# baseboard.net
KiCad netlist of a schematic drawn in EAGLE
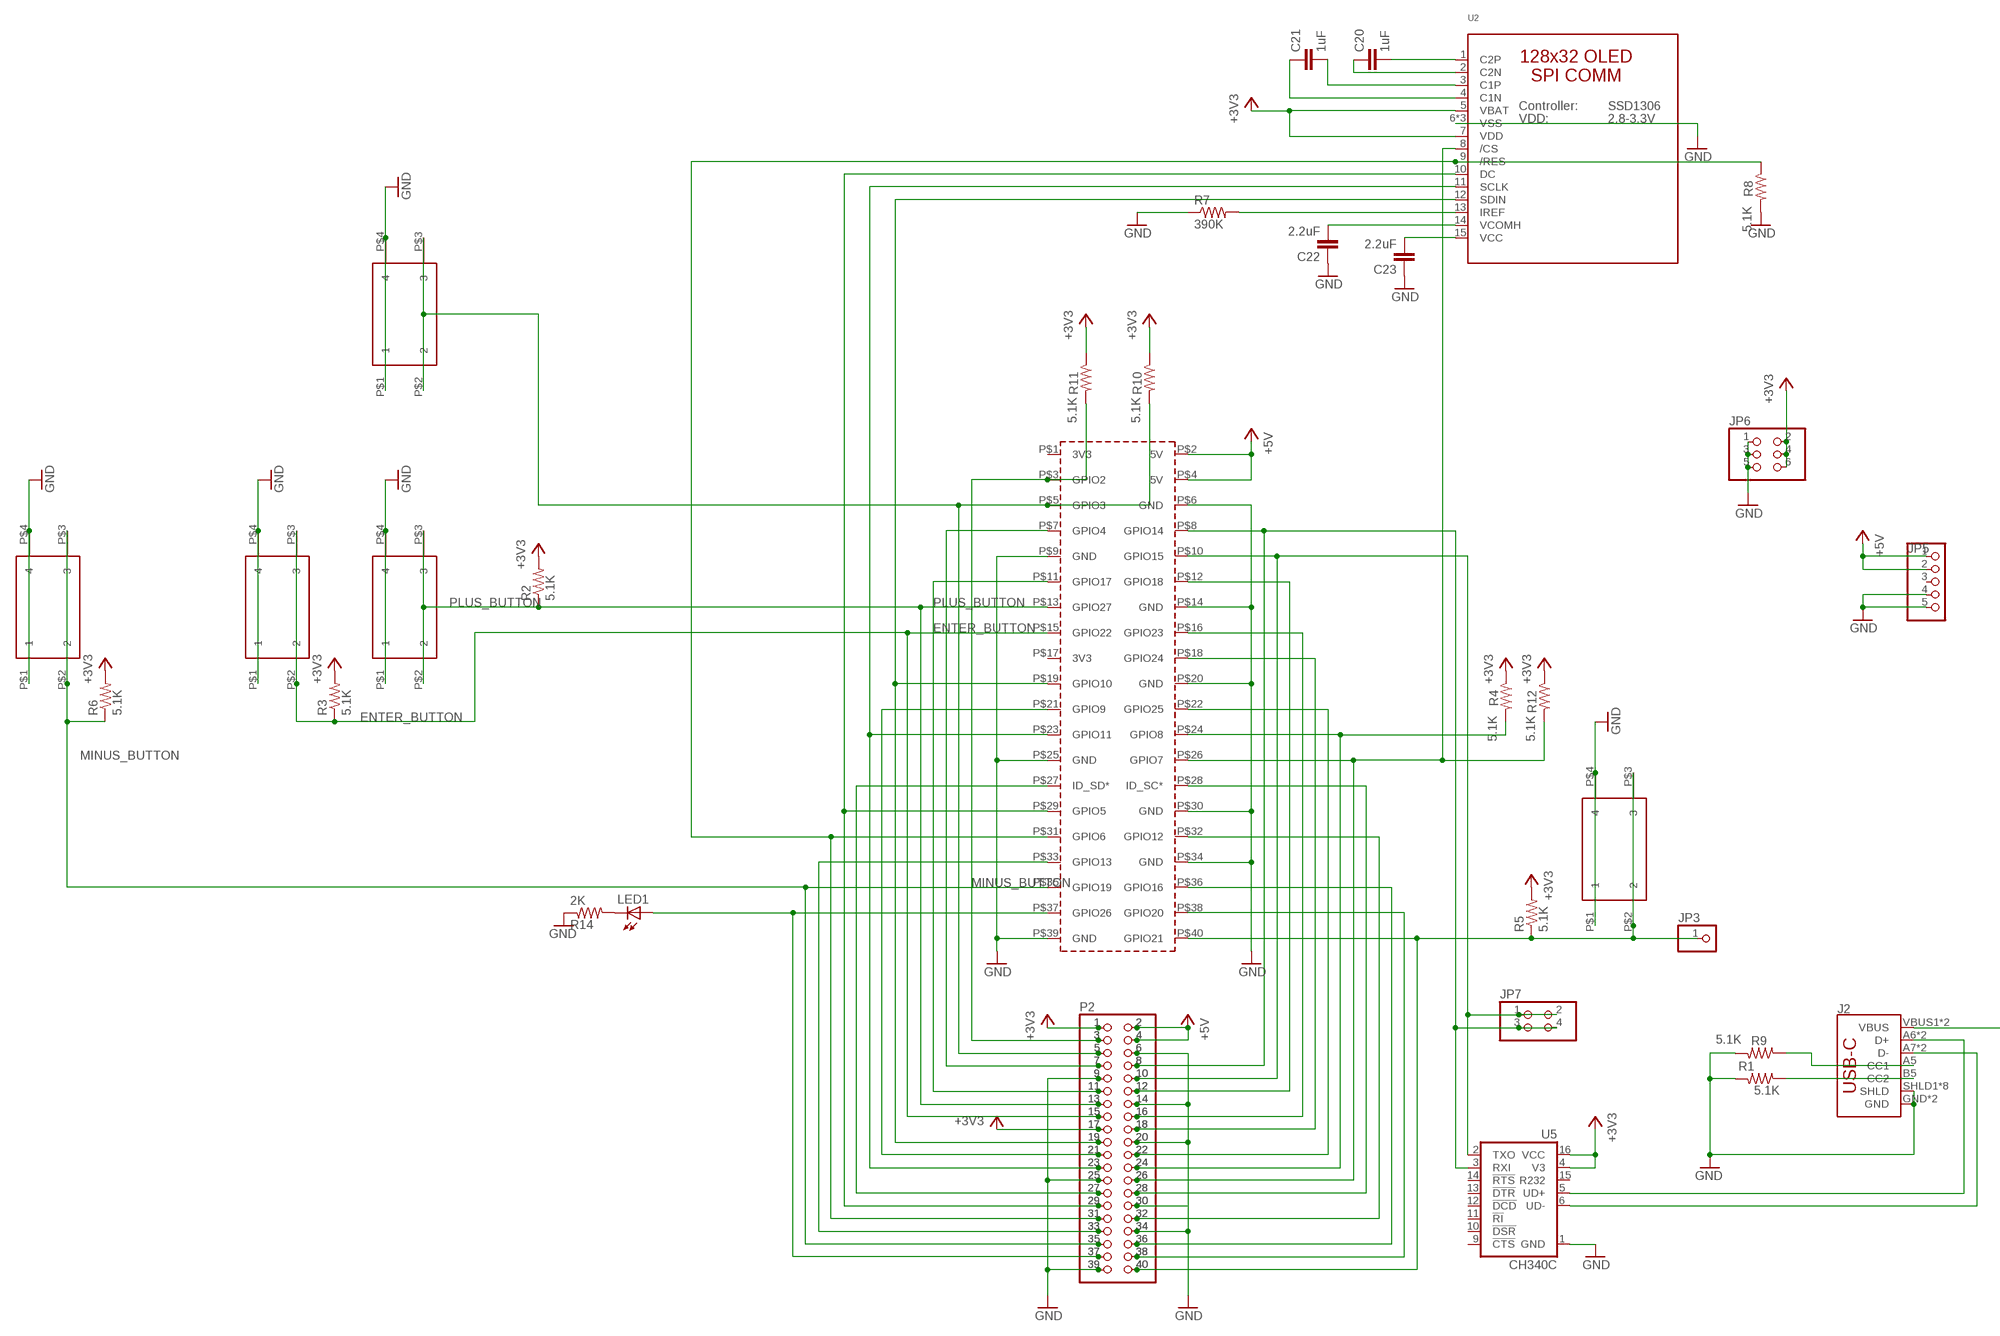
[diagram p0: schematic, sheet 1, part 1 of 2]
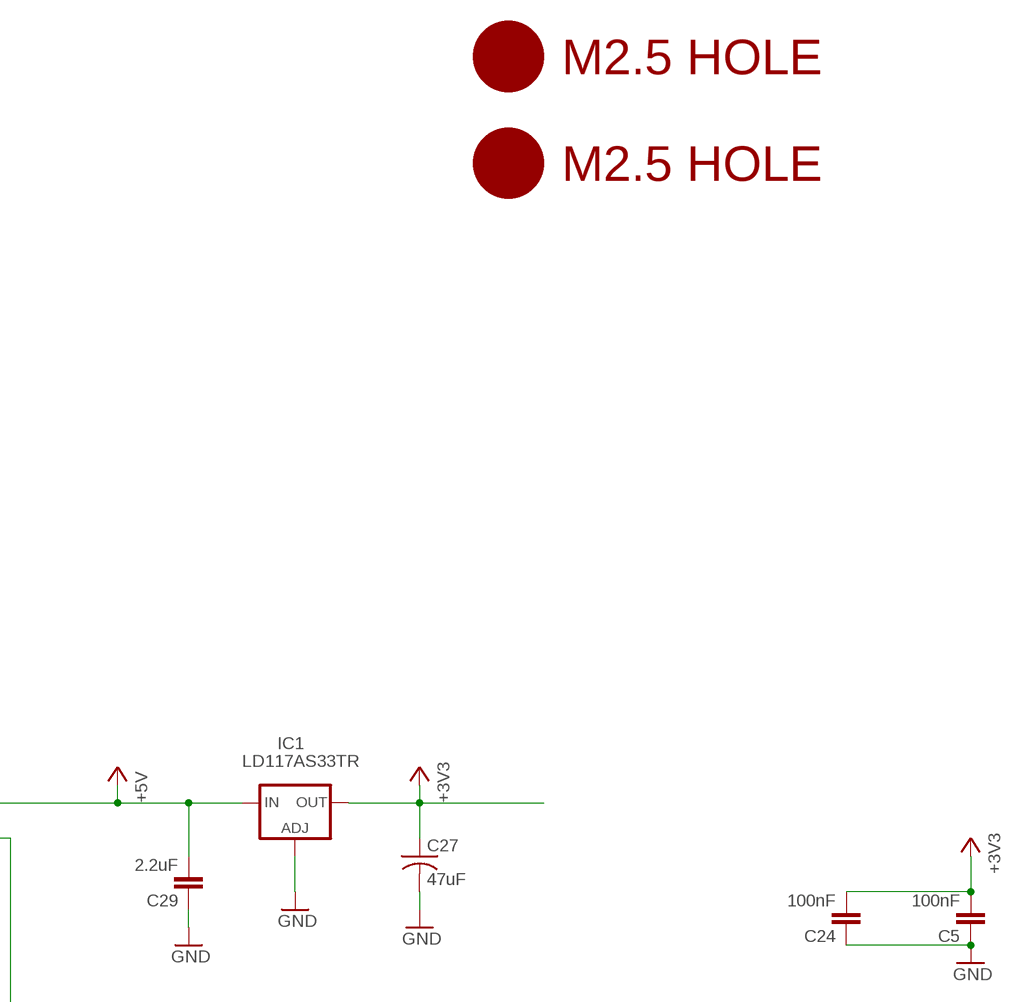
[diagram p1: schematic, sheet 1, part 2 of 2]

(export (version "E")
  (design (tool "Eeschema 10.0.6"))
  (components
    (comp (ref "C5")
      (value "100nF")
      (footprint "eagle-import:0805")
      (libsource (lib "eagle-import") (part "CAP0805"))
    )
    (comp (ref "C20")
      (value "1uF")
      (footprint "eagle-import:0805")
      (libsource (lib "eagle-import") (part "CAP0805"))
    )
    (comp (ref "C21")
      (value "1uF")
      (footprint "eagle-import:0805")
      (libsource (lib "eagle-import") (part "CAP0805"))
    )
    (comp (ref "C22")
      (value "2.2uF")
      (footprint "eagle-import:0805")
      (libsource (lib "eagle-import") (part "CAP0805"))
    )
    (comp (ref "C23")
      (value "2.2uF")
      (footprint "eagle-import:0805")
      (libsource (lib "eagle-import") (part "CAP0805"))
    )
    (comp (ref "C24")
      (value "100nF")
      (footprint "eagle-import:0805")
      (libsource (lib "eagle-import") (part "CAP0805"))
    )
    (comp (ref "C27")
      (value "47uF")
      (footprint "eagle-import:C1210")
      (libsource (lib "eagle-import") (part "C-USC1210"))
    )
    (comp (ref "C29")
      (value "2.2uF")
      (footprint "eagle-import:0805")
      (libsource (lib "eagle-import") (part "CAP0805"))
    )
    (comp (ref "IC1")
      (value "LD117AS33TR")
      (footprint "eagle-import:SOT223")
      (libsource (lib "eagle-import") (part "LD117A?S33TR"))
    )
    (comp (ref "J2")
      (value "USB_C16PIN")
      (footprint "eagle-import:USB-C-16P")
      (libsource (lib "eagle-import") (part "USB_C16PIN"))
    )
    (comp (ref "JP3")
      (value "PINHD-1X1")
      (footprint "eagle-import:1X01")
      (libsource (lib "eagle-import") (part "PINHD-1X1"))
    )
    (comp (ref "JP5")
      (value "PINHD-1X5")
      (footprint "eagle-import:1X05")
      (libsource (lib "eagle-import") (part "PINHD-1X5"))
    )
    (comp (ref "JP6")
      (value "PINHD-2X3")
      (footprint "eagle-import:2X03")
      (libsource (lib "eagle-import") (part "PINHD-2X3"))
    )
    (comp (ref "JP7")
      (value "PINHD-2X2")
      (footprint "eagle-import:2X02")
      (libsource (lib "eagle-import") (part "PINHD-2X2"))
    )
    (comp (ref "LED1")
      (value "LEDCHIP-LED0805")
      (footprint "eagle-import:CHIP-LED0805")
      (libsource (lib "eagle-import") (part "LEDCHIP-LED0805"))
    )
    (comp (ref "P1")
      (value "RPI3NO-CONNECTORS")
      (footprint "eagle-import:RPI3-NO-CONNECTORS")
      (libsource (lib "eagle-import") (part "RPI3NO-CONNECTORS"))
    )
    (comp (ref "P2")
      (value "PINHD-2X20-BIG")
      (footprint "eagle-import:2X20-BIG")
      (libsource (lib "eagle-import") (part "PINHD-2X20-BIG"))
    )
    (comp (ref "P3")
      (value "PINHD-2X20-BIG")
      (footprint "eagle-import:2X20-BIG")
      (libsource (lib "eagle-import") (part "PINHD-2X20-BIG"))
    )
    (comp (ref "R1")
      (value "5.1K")
      (footprint "eagle-import:0805")
      (libsource (lib "eagle-import") (part "joyAnalog_RESISTOR0805-RES"))
    )
    (comp (ref "R2")
      (value "5.1K")
      (footprint "eagle-import:0805")
      (libsource (lib "eagle-import") (part "RESISTOR0805-RES"))
    )
    (comp (ref "R3")
      (value "5.1K")
      (footprint "eagle-import:0805")
      (libsource (lib "eagle-import") (part "RESISTOR0805-RES"))
    )
    (comp (ref "R4")
      (value "5.1K")
      (footprint "eagle-import:0805")
      (libsource (lib "eagle-import") (part "joyAnalog_RESISTOR0805-RES"))
    )
    (comp (ref "R5")
      (value "5.1K")
      (footprint "eagle-import:0805")
      (libsource (lib "eagle-import") (part "RESISTOR0805-RES"))
    )
    (comp (ref "R6")
      (value "5.1K")
      (footprint "eagle-import:0805")
      (libsource (lib "eagle-import") (part "RESISTOR0805-RES"))
    )
    (comp (ref "R7")
      (value "390K")
      (footprint "eagle-import:0805")
      (libsource (lib "eagle-import") (part "RESISTOR0805-RES"))
    )
    (comp (ref "R8")
      (value "5.1K")
      (footprint "eagle-import:0805")
      (libsource (lib "eagle-import") (part "joyAnalog_RESISTOR0805-RES"))
    )
    (comp (ref "R9")
      (value "5.1K")
      (footprint "eagle-import:0805")
      (libsource (lib "eagle-import") (part "joyAnalog_RESISTOR0805-RES"))
    )
    (comp (ref "R10")
      (value "5.1K")
      (footprint "eagle-import:0805")
      (libsource (lib "eagle-import") (part "joyAnalog_RESISTOR0805-RES"))
    )
    (comp (ref "R11")
      (value "5.1K")
      (footprint "eagle-import:0805")
      (libsource (lib "eagle-import") (part "joyAnalog_RESISTOR0805-RES"))
    )
    (comp (ref "R12")
      (value "5.1K")
      (footprint "eagle-import:0805")
      (libsource (lib "eagle-import") (part "joyAnalog_RESISTOR0805-RES"))
    )
    (comp (ref "R14")
      (value "2K")
      (footprint "eagle-import:0805")
      (libsource (lib "eagle-import") (part "RESISTOR0805-RES"))
    )
    (comp (ref "SW1")
      (value "324_SW")
      (footprint "eagle-import:342_SWICH_FOOT")
      (libsource (lib "eagle-import") (part "324_SW"))
    )
    (comp (ref "SW2")
      (value "324_SW")
      (footprint "eagle-import:342_SWICH_FOOT")
      (libsource (lib "eagle-import") (part "324_SW"))
    )
    (comp (ref "SW3")
      (value "324_SW")
      (footprint "eagle-import:342_SWICH_FOOT")
      (libsource (lib "eagle-import") (part "324_SW"))
    )
    (comp (ref "SW4")
      (value "324_SW")
      (footprint "eagle-import:342_SWICH_FOOT")
      (libsource (lib "eagle-import") (part "324_SW"))
    )
    (comp (ref "SW20")
      (value "324_SW")
      (footprint "eagle-import:342_SWICH_FOOT")
      (libsource (lib "eagle-import") (part "324_SW"))
    )
    (comp (ref "U$2")
      (value "M2.5HOLE")
      (footprint "eagle-import:M2.5HOLE")
      (libsource (lib "eagle-import") (part "M2.5HOLE"))
    )
    (comp (ref "U$3")
      (value "M2.5HOLE")
      (footprint "eagle-import:M2.5HOLE")
      (libsource (lib "eagle-import") (part "M2.5HOLE"))
    )
    (comp (ref "U2")
      (value "LUL_DISP_OLED_UG-2864HSWEG01")
      (footprint "eagle-import:LUL_UG-2864HSWEG01_1.3_WRAPAROUND")
      (libsource (lib "eagle-import") (part "LUL_DISP_OLED_UG-2864HSWEG01"))
    )
    (comp (ref "U5")
      (value "CH340C")
      (footprint "eagle-import:SO016")
      (libsource (lib "eagle-import") (part "CH340C"))
    )
  )
  (nets
    (net (code "1") (name "+3V3") (class "Default")
      (node (ref "C24") (pin "2") (pinfunction "2_2") (pintype "passive"))
      (node (ref "C27") (pin "1") (pinfunction "1_1") (pintype "passive"))
      (node (ref "C5") (pin "2") (pinfunction "2_2") (pintype "passive"))
      (node (ref "IC1") (pin "4") (pinfunction "OUT_4") (pintype "passive"))
      (node (ref "JP6") (pin "2") (pinfunction "2_2") (pintype "passive"))
      (node (ref "JP6") (pin "4") (pinfunction "4_4") (pintype "passive"))
      (node (ref "JP6") (pin "6") (pinfunction "6_6") (pintype "passive"))
      (node (ref "P2") (pin "1") (pinfunction "1_1") (pintype "passive"))
      (node (ref "P2") (pin "17") (pinfunction "17_17") (pintype "passive"))
      (node (ref "P3") (pin "1") (pinfunction "1_1") (pintype "passive"))
      (node (ref "P3") (pin "17") (pinfunction "17_17") (pintype "passive"))
      (node (ref "R10") (pin "1") (pinfunction "1_1") (pintype "passive"))
      (node (ref "R11") (pin "1") (pinfunction "1_1") (pintype "passive"))
      (node (ref "R12") (pin "1") (pinfunction "1_1") (pintype "passive"))
      (node (ref "R2") (pin "2") (pinfunction "2_2") (pintype "passive"))
      (node (ref "R3") (pin "2") (pinfunction "2_2") (pintype "passive"))
      (node (ref "R4") (pin "1") (pinfunction "1_1") (pintype "passive"))
      (node (ref "R5") (pin "2") (pinfunction "2_2") (pintype "passive"))
      (node (ref "R6") (pin "2") (pinfunction "2_2") (pintype "passive"))
      (node (ref "U2") (pin "5") (pinfunction "VBAT_5") (pintype "input"))
      (node (ref "U2") (pin "7") (pinfunction "VDD_7") (pintype "power_in"))
      (node (ref "U5") (pin "16") (pinfunction "VCC_16") (pintype "bidirectional"))
      (node (ref "U5") (pin "4") (pinfunction "V3_4") (pintype "bidirectional"))
    )
    (net (code "2") (name "+5V") (class "Default")
      (node (ref "C29") (pin "2") (pinfunction "2_2") (pintype "passive"))
      (node (ref "IC1") (pin "3") (pinfunction "IN_3") (pintype "input"))
      (node (ref "J2") (pin "VBUS1") (pinfunction "VBUS_VBUS1") (pintype "bidirectional"))
      (node (ref "J2") (pin "VBUS2") (pinfunction "VBUS_VBUS2") (pintype "bidirectional"))
      (node (ref "JP5") (pin "1") (pinfunction "1_1") (pintype "passive"))
      (node (ref "JP5") (pin "2") (pinfunction "2_2") (pintype "passive"))
      (node (ref "P1") (pin "P$2") (pinfunction "5V_P$2") (pintype "bidirectional"))
      (node (ref "P1") (pin "P$4") (pinfunction "5V_P$4") (pintype "bidirectional"))
      (node (ref "P2") (pin "2") (pinfunction "2_2") (pintype "passive"))
      (node (ref "P2") (pin "4") (pinfunction "4_4") (pintype "passive"))
      (node (ref "P3") (pin "2") (pinfunction "2_2") (pintype "passive"))
      (node (ref "P3") (pin "4") (pinfunction "4_4") (pintype "passive"))
    )
    (net (code "3") (name "/ENTER_BUTTON") (class "Default")
      (node (ref "P1") (pin "P$15") (pinfunction "GPIO22_P$15") (pintype "bidirectional"))
      (node (ref "P2") (pin "15") (pinfunction "15_15") (pintype "passive"))
      (node (ref "P3") (pin "15") (pinfunction "15_15") (pintype "passive"))
      (node (ref "R3") (pin "1") (pinfunction "1_1") (pintype "passive"))
      (node (ref "SW20") (pin "P$2") (pinfunction "2_P$2") (pintype "bidirectional"))
      (node (ref "SW20") (pin "P$3") (pinfunction "3_P$3") (pintype "bidirectional"))
    )
    (net (code "4") (name "/MINUS_BUTTON") (class "Default")
      (node (ref "P1") (pin "P$35") (pinfunction "GPIO19_P$35") (pintype "bidirectional"))
      (node (ref "P2") (pin "35") (pinfunction "35_35") (pintype "passive"))
      (node (ref "P3") (pin "35") (pinfunction "35_35") (pintype "passive"))
      (node (ref "R6") (pin "1") (pinfunction "1_1") (pintype "passive"))
      (node (ref "SW4") (pin "P$2") (pinfunction "2_P$2") (pintype "bidirectional"))
      (node (ref "SW4") (pin "P$3") (pinfunction "3_P$3") (pintype "bidirectional"))
    )
    (net (code "5") (name "/PLUS_BUTTON") (class "Default")
      (node (ref "P1") (pin "P$13") (pinfunction "GPIO27_P$13") (pintype "bidirectional"))
      (node (ref "P2") (pin "13") (pinfunction "13_13") (pintype "passive"))
      (node (ref "P3") (pin "13") (pinfunction "13_13") (pintype "passive"))
      (node (ref "R2") (pin "1") (pinfunction "1_1") (pintype "passive"))
      (node (ref "SW1") (pin "P$2") (pinfunction "2_P$2") (pintype "bidirectional"))
      (node (ref "SW1") (pin "P$3") (pinfunction "3_P$3") (pintype "bidirectional"))
    )
    (net (code "6") (name "GND") (class "Default")
      (node (ref "C22") (pin "1") (pinfunction "1_1") (pintype "passive"))
      (node (ref "C23") (pin "1") (pinfunction "1_1") (pintype "passive"))
      (node (ref "C24") (pin "1") (pinfunction "1_1") (pintype "passive"))
      (node (ref "C27") (pin "2") (pinfunction "2_2") (pintype "passive"))
      (node (ref "C29") (pin "1") (pinfunction "1_1") (pintype "passive"))
      (node (ref "C5") (pin "1") (pinfunction "1_1") (pintype "passive"))
      (node (ref "IC1") (pin "1") (pinfunction "ADJ_1") (pintype "input"))
      (node (ref "J2") (pin "GND") (pinfunction "GND_GND") (pintype "bidirectional"))
      (node (ref "J2") (pin "GND2") (pinfunction "GND_GND2") (pintype "bidirectional"))
      (node (ref "J2") (pin "SHLD1") (pinfunction "SHLD_SHLD1") (pintype "bidirectional"))
      (node (ref "J2") (pin "SHLD2") (pinfunction "SHLD_SHLD2") (pintype "bidirectional"))
      (node (ref "J2") (pin "SHLD3") (pinfunction "SHLD_SHLD3") (pintype "bidirectional"))
      (node (ref "J2") (pin "SHLD4") (pinfunction "SHLD_SHLD4") (pintype "bidirectional"))
      (node (ref "J2") (pin "SHLD5") (pinfunction "SHLD_SHLD5") (pintype "bidirectional"))
      (node (ref "J2") (pin "SHLD6") (pinfunction "SHLD_SHLD6") (pintype "bidirectional"))
      (node (ref "J2") (pin "SHLD7") (pinfunction "SHLD_SHLD7") (pintype "bidirectional"))
      (node (ref "J2") (pin "SHLD8") (pinfunction "SHLD_SHLD8") (pintype "bidirectional"))
      (node (ref "JP5") (pin "4") (pinfunction "4_4") (pintype "passive"))
      (node (ref "JP5") (pin "5") (pinfunction "5_5") (pintype "passive"))
      (node (ref "JP6") (pin "1") (pinfunction "1_1") (pintype "passive"))
      (node (ref "JP6") (pin "3") (pinfunction "3_3") (pintype "passive"))
      (node (ref "JP6") (pin "5") (pinfunction "5_5") (pintype "passive"))
      (node (ref "P1") (pin "P$14") (pinfunction "GND_P$14") (pintype "bidirectional"))
      (node (ref "P1") (pin "P$20") (pinfunction "GND_P$20") (pintype "bidirectional"))
      (node (ref "P1") (pin "P$25") (pinfunction "GND_P$25") (pintype "bidirectional"))
      (node (ref "P1") (pin "P$30") (pinfunction "GND_P$30") (pintype "bidirectional"))
      (node (ref "P1") (pin "P$34") (pinfunction "GND_P$34") (pintype "bidirectional"))
      (node (ref "P1") (pin "P$39") (pinfunction "GND_P$39") (pintype "bidirectional"))
      (node (ref "P1") (pin "P$6") (pinfunction "GND_P$6") (pintype "bidirectional"))
      (node (ref "P1") (pin "P$9") (pinfunction "GND_P$9") (pintype "bidirectional"))
      (node (ref "P2") (pin "14") (pinfunction "14_14") (pintype "passive"))
      (node (ref "P2") (pin "20") (pinfunction "20_20") (pintype "passive"))
      (node (ref "P2") (pin "25") (pinfunction "25_25") (pintype "passive"))
      (node (ref "P2") (pin "30") (pinfunction "30_30") (pintype "passive"))
      (node (ref "P2") (pin "34") (pinfunction "34_34") (pintype "passive"))
      (node (ref "P2") (pin "39") (pinfunction "39_39") (pintype "passive"))
      (node (ref "P2") (pin "6") (pinfunction "6_6") (pintype "passive"))
      (node (ref "P2") (pin "9") (pinfunction "9_9") (pintype "passive"))
      (node (ref "P3") (pin "14") (pinfunction "14_14") (pintype "passive"))
      (node (ref "P3") (pin "20") (pinfunction "20_20") (pintype "passive"))
      (node (ref "P3") (pin "25") (pinfunction "25_25") (pintype "passive"))
      (node (ref "P3") (pin "30") (pinfunction "30_30") (pintype "passive"))
      (node (ref "P3") (pin "34") (pinfunction "34_34") (pintype "passive"))
      (node (ref "P3") (pin "39") (pinfunction "39_39") (pintype "passive"))
      (node (ref "P3") (pin "6") (pinfunction "6_6") (pintype "passive"))
      (node (ref "P3") (pin "9") (pinfunction "9_9") (pintype "passive"))
      (node (ref "R1") (pin "2") (pinfunction "2_2") (pintype "passive"))
      (node (ref "R14") (pin "1") (pinfunction "1_1") (pintype "passive"))
      (node (ref "R7") (pin "1") (pinfunction "1_1") (pintype "passive"))
      (node (ref "R8") (pin "2") (pinfunction "2_2") (pintype "passive"))
      (node (ref "R9") (pin "2") (pinfunction "2_2") (pintype "passive"))
      (node (ref "SW1") (pin "P$1") (pinfunction "1_P$1") (pintype "bidirectional"))
      (node (ref "SW1") (pin "P$4") (pinfunction "4_P$4") (pintype "bidirectional"))
      (node (ref "SW2") (pin "P$1") (pinfunction "1_P$1") (pintype "bidirectional"))
      (node (ref "SW2") (pin "P$4") (pinfunction "4_P$4") (pintype "bidirectional"))
      (node (ref "SW20") (pin "P$1") (pinfunction "1_P$1") (pintype "bidirectional"))
      (node (ref "SW20") (pin "P$4") (pinfunction "4_P$4") (pintype "bidirectional"))
      (node (ref "SW3") (pin "P$1") (pinfunction "1_P$1") (pintype "bidirectional"))
      (node (ref "SW3") (pin "P$4") (pinfunction "4_P$4") (pintype "bidirectional"))
      (node (ref "SW4") (pin "P$1") (pinfunction "1_P$1") (pintype "bidirectional"))
      (node (ref "SW4") (pin "P$4") (pinfunction "4_P$4") (pintype "bidirectional"))
      (node (ref "U2") (pin "16") (pinfunction "VSS_16") (pintype "power_in"))
      (node (ref "U2") (pin "17") (pinfunction "VSS_17") (pintype "power_in"))
      (node (ref "U2") (pin "6") (pinfunction "VSS_6") (pintype "power_in"))
      (node (ref "U5") (pin "1") (pinfunction "GND_1") (pintype "bidirectional"))
    )
    (net (code "7") (name "Net-(J2-CC1)") (class "Default")
      (node (ref "J2") (pin "A5") (pinfunction "CC1_A5") (pintype "bidirectional"))
      (node (ref "R9") (pin "1") (pinfunction "1_1") (pintype "passive"))
    )
    (net (code "8") (name "Net-(J2-CC2)") (class "Default")
      (node (ref "J2") (pin "B5") (pinfunction "CC2_B5") (pintype "bidirectional"))
      (node (ref "R1") (pin "1") (pinfunction "1_1") (pintype "passive"))
    )
    (net (code "9") (name "Net-(LED1-PadC)") (class "Default")
      (node (ref "LED1") (pin "C") (pinfunction "C_C") (pintype "passive"))
      (node (ref "R14") (pin "2") (pinfunction "2_2") (pintype "passive"))
    )
    (net (code "10") (name "Net-(P1-GPIO2)") (class "Default")
      (node (ref "P1") (pin "P$3") (pinfunction "GPIO2_P$3") (pintype "bidirectional"))
      (node (ref "P2") (pin "3") (pinfunction "3_3") (pintype "passive"))
      (node (ref "P3") (pin "3") (pinfunction "3_3") (pintype "passive"))
      (node (ref "R11") (pin "2") (pinfunction "2_2") (pintype "passive"))
    )
    (net (code "11") (name "Net-(P1-GPIO3)") (class "Default")
      (node (ref "P1") (pin "P$5") (pinfunction "GPIO3_P$5") (pintype "bidirectional"))
      (node (ref "P2") (pin "5") (pinfunction "5_5") (pintype "passive"))
      (node (ref "P3") (pin "5") (pinfunction "5_5") (pintype "passive"))
      (node (ref "R10") (pin "2") (pinfunction "2_2") (pintype "passive"))
      (node (ref "SW2") (pin "P$2") (pinfunction "2_P$2") (pintype "bidirectional"))
      (node (ref "SW2") (pin "P$3") (pinfunction "3_P$3") (pintype "bidirectional"))
    )
    (net (code "12") (name "Net-(P1-GPIO4)") (class "Default")
      (node (ref "P1") (pin "P$7") (pinfunction "GPIO4_P$7") (pintype "bidirectional"))
      (node (ref "P2") (pin "7") (pinfunction "7_7") (pintype "passive"))
      (node (ref "P3") (pin "7") (pinfunction "7_7") (pintype "passive"))
    )
    (net (code "13") (name "Net-(P1-GPIO5)") (class "Default")
      (node (ref "P1") (pin "P$29") (pinfunction "GPIO5_P$29") (pintype "bidirectional"))
      (node (ref "P2") (pin "29") (pinfunction "29_29") (pintype "passive"))
      (node (ref "P3") (pin "29") (pinfunction "29_29") (pintype "passive"))
      (node (ref "U2") (pin "10") (pinfunction "DC_10") (pintype "input"))
    )
    (net (code "14") (name "Net-(P1-GPIO6)") (class "Default")
      (node (ref "P1") (pin "P$31") (pinfunction "GPIO6_P$31") (pintype "bidirectional"))
      (node (ref "P2") (pin "31") (pinfunction "31_31") (pintype "passive"))
      (node (ref "P3") (pin "31") (pinfunction "31_31") (pintype "passive"))
      (node (ref "R8") (pin "1") (pinfunction "1_1") (pintype "passive"))
      (node (ref "U2") (pin "9") (pinfunction "/RES_9") (pintype "input"))
    )
    (net (code "15") (name "Net-(P1-GPIO7)") (class "Default")
      (node (ref "P1") (pin "P$26") (pinfunction "GPIO7_P$26") (pintype "bidirectional"))
      (node (ref "P2") (pin "26") (pinfunction "26_26") (pintype "passive"))
      (node (ref "P3") (pin "26") (pinfunction "26_26") (pintype "passive"))
      (node (ref "R12") (pin "2") (pinfunction "2_2") (pintype "passive"))
      (node (ref "U2") (pin "8") (pinfunction "/CS_8") (pintype "input"))
    )
    (net (code "16") (name "Net-(P1-GPIO8)") (class "Default")
      (node (ref "P1") (pin "P$24") (pinfunction "GPIO8_P$24") (pintype "bidirectional"))
      (node (ref "P2") (pin "24") (pinfunction "24_24") (pintype "passive"))
      (node (ref "P3") (pin "24") (pinfunction "24_24") (pintype "passive"))
      (node (ref "R4") (pin "2") (pinfunction "2_2") (pintype "passive"))
    )
    (net (code "17") (name "Net-(P1-GPIO9)") (class "Default")
      (node (ref "P1") (pin "P$21") (pinfunction "GPIO9_P$21") (pintype "bidirectional"))
      (node (ref "P2") (pin "21") (pinfunction "21_21") (pintype "passive"))
      (node (ref "P3") (pin "21") (pinfunction "21_21") (pintype "passive"))
    )
    (net (code "18") (name "Net-(P1-GPIO10)") (class "Default")
      (node (ref "P1") (pin "P$19") (pinfunction "GPIO10_P$19") (pintype "bidirectional"))
      (node (ref "P2") (pin "19") (pinfunction "19_19") (pintype "passive"))
      (node (ref "P3") (pin "19") (pinfunction "19_19") (pintype "passive"))
      (node (ref "U2") (pin "12") (pinfunction "SDIN_12") (pintype "bidirectional"))
    )
    (net (code "19") (name "Net-(P1-GPIO11)") (class "Default")
      (node (ref "P1") (pin "P$23") (pinfunction "GPIO11_P$23") (pintype "bidirectional"))
      (node (ref "P2") (pin "23") (pinfunction "23_23") (pintype "passive"))
      (node (ref "P3") (pin "23") (pinfunction "23_23") (pintype "passive"))
      (node (ref "U2") (pin "11") (pinfunction "SCLK_11") (pintype "bidirectional"))
    )
    (net (code "20") (name "Net-(P1-GPIO12)") (class "Default")
      (node (ref "P1") (pin "P$32") (pinfunction "GPIO12_P$32") (pintype "bidirectional"))
      (node (ref "P2") (pin "32") (pinfunction "32_32") (pintype "passive"))
      (node (ref "P3") (pin "32") (pinfunction "32_32") (pintype "passive"))
    )
    (net (code "21") (name "Net-(P1-GPIO13)") (class "Default")
      (node (ref "P1") (pin "P$33") (pinfunction "GPIO13_P$33") (pintype "bidirectional"))
      (node (ref "P2") (pin "33") (pinfunction "33_33") (pintype "passive"))
      (node (ref "P3") (pin "33") (pinfunction "33_33") (pintype "passive"))
    )
    (net (code "22") (name "Net-(P1-GPIO14)") (class "Default")
      (node (ref "JP7") (pin "3") (pinfunction "3_3") (pintype "passive"))
      (node (ref "JP7") (pin "4") (pinfunction "4_4") (pintype "passive"))
      (node (ref "P1") (pin "P$8") (pinfunction "GPIO14_P$8") (pintype "bidirectional"))
      (node (ref "P2") (pin "8") (pinfunction "8_8") (pintype "passive"))
      (node (ref "P3") (pin "8") (pinfunction "8_8") (pintype "passive"))
      (node (ref "U5") (pin "3") (pinfunction "RXI_3") (pintype "bidirectional"))
    )
    (net (code "23") (name "Net-(P1-GPIO15)") (class "Default")
      (node (ref "JP7") (pin "1") (pinfunction "1_1") (pintype "passive"))
      (node (ref "JP7") (pin "2") (pinfunction "2_2") (pintype "passive"))
      (node (ref "P1") (pin "P$10") (pinfunction "GPIO15_P$10") (pintype "bidirectional"))
      (node (ref "P2") (pin "10") (pinfunction "10_10") (pintype "passive"))
      (node (ref "P3") (pin "10") (pinfunction "10_10") (pintype "passive"))
      (node (ref "U5") (pin "2") (pinfunction "TXO_2") (pintype "bidirectional"))
    )
    (net (code "24") (name "Net-(P1-GPIO16)") (class "Default")
      (node (ref "P1") (pin "P$36") (pinfunction "GPIO16_P$36") (pintype "bidirectional"))
      (node (ref "P2") (pin "36") (pinfunction "36_36") (pintype "passive"))
      (node (ref "P3") (pin "36") (pinfunction "36_36") (pintype "passive"))
    )
    (net (code "25") (name "Net-(P1-GPIO17)") (class "Default")
      (node (ref "P1") (pin "P$11") (pinfunction "GPIO17_P$11") (pintype "bidirectional"))
      (node (ref "P2") (pin "11") (pinfunction "11_11") (pintype "passive"))
      (node (ref "P3") (pin "11") (pinfunction "11_11") (pintype "passive"))
    )
    (net (code "26") (name "Net-(P1-GPIO18)") (class "Default")
      (node (ref "P1") (pin "P$12") (pinfunction "GPIO18_P$12") (pintype "bidirectional"))
      (node (ref "P2") (pin "12") (pinfunction "12_12") (pintype "passive"))
      (node (ref "P3") (pin "12") (pinfunction "12_12") (pintype "passive"))
    )
    (net (code "27") (name "Net-(P1-GPIO20)") (class "Default")
      (node (ref "P1") (pin "P$38") (pinfunction "GPIO20_P$38") (pintype "bidirectional"))
      (node (ref "P2") (pin "38") (pinfunction "38_38") (pintype "passive"))
      (node (ref "P3") (pin "38") (pinfunction "38_38") (pintype "passive"))
    )
    (net (code "28") (name "Net-(P1-GPIO21)") (class "Default")
      (node (ref "JP3") (pin "1") (pinfunction "1_1") (pintype "passive"))
      (node (ref "P1") (pin "P$40") (pinfunction "GPIO21_P$40") (pintype "bidirectional"))
      (node (ref "P2") (pin "40") (pinfunction "40_40") (pintype "passive"))
      (node (ref "P3") (pin "40") (pinfunction "40_40") (pintype "passive"))
      (node (ref "R5") (pin "1") (pinfunction "1_1") (pintype "passive"))
      (node (ref "SW3") (pin "P$2") (pinfunction "2_P$2") (pintype "bidirectional"))
      (node (ref "SW3") (pin "P$3") (pinfunction "3_P$3") (pintype "bidirectional"))
    )
    (net (code "29") (name "Net-(P1-GPIO23)") (class "Default")
      (node (ref "P1") (pin "P$16") (pinfunction "GPIO23_P$16") (pintype "bidirectional"))
      (node (ref "P2") (pin "16") (pinfunction "16_16") (pintype "passive"))
      (node (ref "P3") (pin "16") (pinfunction "16_16") (pintype "passive"))
    )
    (net (code "30") (name "Net-(P1-GPIO24)") (class "Default")
      (node (ref "P1") (pin "P$18") (pinfunction "GPIO24_P$18") (pintype "bidirectional"))
      (node (ref "P2") (pin "18") (pinfunction "18_18") (pintype "passive"))
      (node (ref "P3") (pin "18") (pinfunction "18_18") (pintype "passive"))
    )
    (net (code "31") (name "Net-(P1-GPIO25)") (class "Default")
      (node (ref "P1") (pin "P$22") (pinfunction "GPIO25_P$22") (pintype "bidirectional"))
      (node (ref "P2") (pin "22") (pinfunction "22_22") (pintype "passive"))
      (node (ref "P3") (pin "22") (pinfunction "22_22") (pintype "passive"))
    )
    (net (code "32") (name "Net-(P1-GPIO26)") (class "Default")
      (node (ref "LED1") (pin "A") (pinfunction "A_A") (pintype "passive"))
      (node (ref "P1") (pin "P$37") (pinfunction "GPIO26_P$37") (pintype "bidirectional"))
      (node (ref "P2") (pin "37") (pinfunction "37_37") (pintype "passive"))
      (node (ref "P3") (pin "37") (pinfunction "37_37") (pintype "passive"))
    )
    (net (code "33") (name "Net-(P1-ID_SC*)") (class "Default")
      (node (ref "P1") (pin "P$28") (pinfunction "ID_SC*_P$28") (pintype "bidirectional"))
      (node (ref "P2") (pin "28") (pinfunction "28_28") (pintype "passive"))
      (node (ref "P3") (pin "28") (pinfunction "28_28") (pintype "passive"))
    )
    (net (code "34") (name "Net-(P1-ID_SD*)") (class "Default")
      (node (ref "P1") (pin "P$27") (pinfunction "ID_SD*_P$27") (pintype "bidirectional"))
      (node (ref "P2") (pin "27") (pinfunction "27_27") (pintype "passive"))
      (node (ref "P3") (pin "27") (pinfunction "27_27") (pintype "passive"))
    )
    (net (code "35") (name "Net-(U2-C1N)") (class "Default")
      (node (ref "C21") (pin "1") (pinfunction "1_1") (pintype "passive"))
      (node (ref "U2") (pin "4") (pinfunction "C1N_4") (pintype "input"))
    )
    (net (code "36") (name "Net-(U2-C1P)") (class "Default")
      (node (ref "C21") (pin "2") (pinfunction "2_2") (pintype "passive"))
      (node (ref "U2") (pin "3") (pinfunction "C1P_3") (pintype "input"))
    )
    (net (code "37") (name "Net-(U2-C2N)") (class "Default")
      (node (ref "C20") (pin "1") (pinfunction "1_1") (pintype "passive"))
      (node (ref "U2") (pin "2") (pinfunction "C2N_2") (pintype "input"))
    )
    (net (code "38") (name "Net-(U2-C2P)") (class "Default")
      (node (ref "C20") (pin "2") (pinfunction "2_2") (pintype "passive"))
      (node (ref "U2") (pin "1") (pinfunction "C2P_1") (pintype "input"))
    )
    (net (code "39") (name "Net-(U2-IREF)") (class "Default")
      (node (ref "R7") (pin "2") (pinfunction "2_2") (pintype "passive"))
      (node (ref "U2") (pin "13") (pinfunction "IREF_13") (pintype "input"))
    )
    (net (code "40") (name "Net-(U2-VCC)") (class "Default")
      (node (ref "C23") (pin "2") (pinfunction "2_2") (pintype "passive"))
      (node (ref "U2") (pin "15") (pinfunction "VCC_15") (pintype "power_in"))
    )
    (net (code "41") (name "Net-(U2-VCOMH)") (class "Default")
      (node (ref "C22") (pin "2") (pinfunction "2_2") (pintype "passive"))
      (node (ref "U2") (pin "14") (pinfunction "VCOMH_14") (pintype "output"))
    )
    (net (code "42") (name "Net-(U5-UD+)") (class "Default")
      (node (ref "J2") (pin "A6") (pinfunction "D+_A6") (pintype "bidirectional"))
      (node (ref "J2") (pin "B6") (pinfunction "D+_B6") (pintype "bidirectional"))
      (node (ref "U5") (pin "5") (pinfunction "UD+_5") (pintype "bidirectional"))
    )
    (net (code "43") (name "Net-(U5-UD-)") (class "Default")
      (node (ref "J2") (pin "A7") (pinfunction "D-_A7") (pintype "bidirectional"))
      (node (ref "J2") (pin "B7") (pinfunction "D-_B7") (pintype "bidirectional"))
      (node (ref "U5") (pin "6") (pinfunction "UD-_6") (pintype "bidirectional"))
    )
    (net (code "44") (name "unconnected-(JP5-Pad3)") (class "Default")
      (node (ref "JP5") (pin "3") (pinfunction "3_3") (pintype "passive"))
    )
    (net (code "45") (name "unconnected-(P1-3V3-PadP$1)") (class "Default")
      (node (ref "P1") (pin "P$1") (pinfunction "3V3_P$1") (pintype "bidirectional"))
    )
    (net (code "46") (name "unconnected-(P1-3V3-PadP$17)") (class "Default")
      (node (ref "P1") (pin "P$17") (pinfunction "3V3_P$17") (pintype "bidirectional"))
    )
    (net (code "47") (name "unconnected-(U5-R232-Pad15)") (class "Default")
      (node (ref "U5") (pin "15") (pinfunction "R232_15") (pintype "bidirectional"))
    )
    (net (code "48") (name "unconnected-(U5-~{CTS}-Pad9)") (class "Default")
      (node (ref "U5") (pin "9") (pinfunction "~{CTS}_9") (pintype "bidirectional"))
    )
    (net (code "49") (name "unconnected-(U5-~{DCD}-Pad12)") (class "Default")
      (node (ref "U5") (pin "12") (pinfunction "~{DCD}_12") (pintype "bidirectional"))
    )
    (net (code "50") (name "unconnected-(U5-~{DSR}-Pad10)") (class "Default")
      (node (ref "U5") (pin "10") (pinfunction "~{DSR}_10") (pintype "bidirectional"))
    )
    (net (code "51") (name "unconnected-(U5-~{DTR}-Pad13)") (class "Default")
      (node (ref "U5") (pin "13") (pinfunction "~{DTR}_13") (pintype "bidirectional"))
    )
    (net (code "52") (name "unconnected-(U5-~{RI}-Pad11)") (class "Default")
      (node (ref "U5") (pin "11") (pinfunction "~{RI}_11") (pintype "bidirectional"))
    )
    (net (code "53") (name "unconnected-(U5-~{RTS}-Pad14)") (class "Default")
      (node (ref "U5") (pin "14") (pinfunction "~{RTS}_14") (pintype "bidirectional"))
    )
  )
)
